# Sheet2.net
KiCad netlist of a schematic drawn in Altium Designer
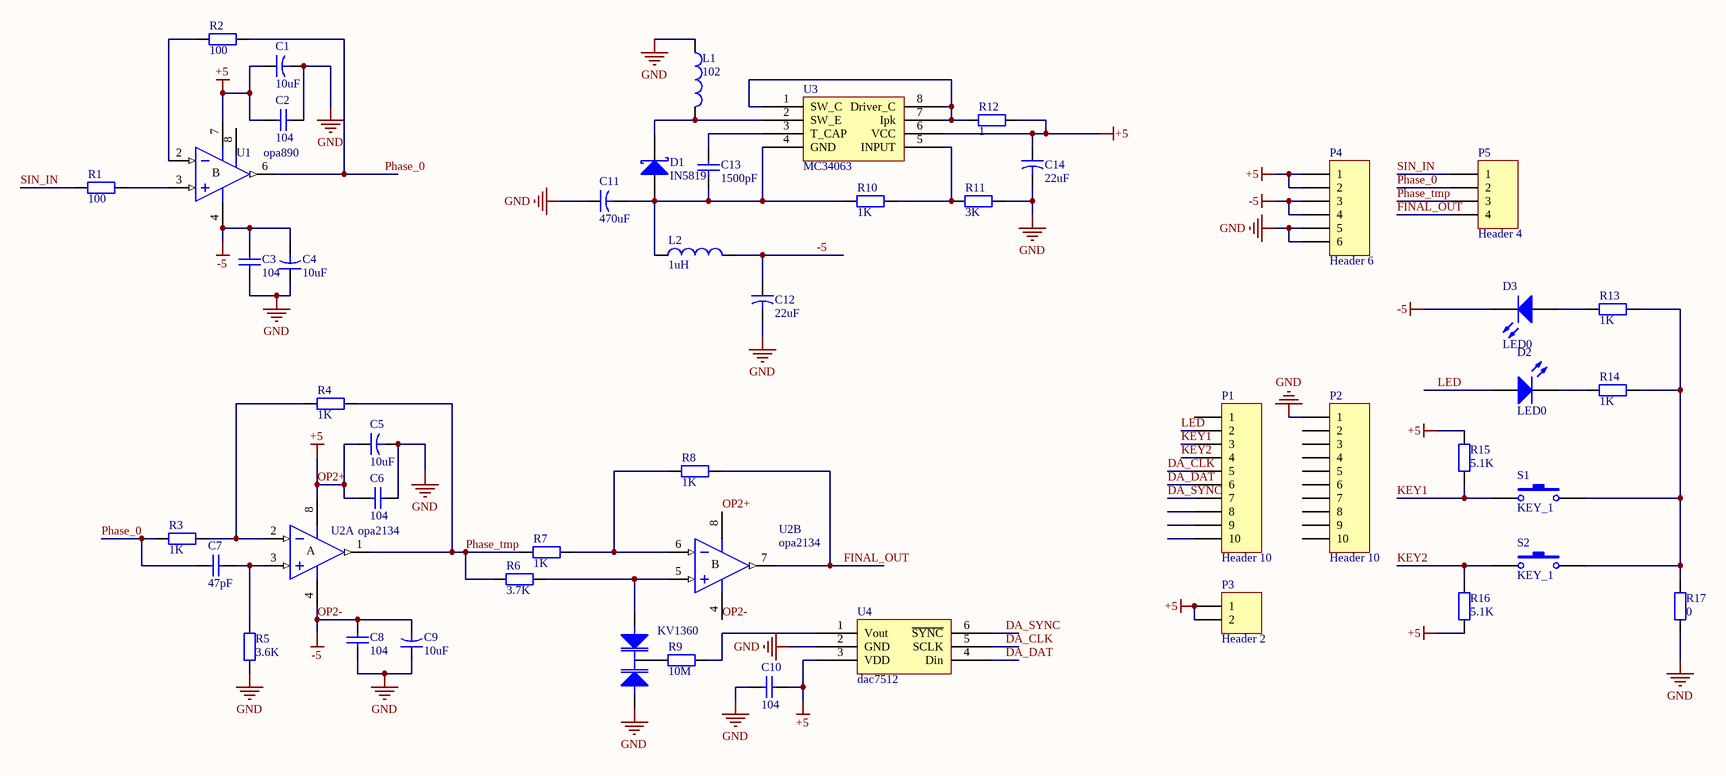
[diagram p0: Sheet2.SchDoc]

(export (version "E")
  (design (tool "Eeschema 10.0.6"))
  (components
    (comp (ref "*") (value "KV1360") (footprint "T092-3") (libsource (lib "暑期学校") (part "KV1360")))
    (comp (ref "C1")
      (value "10uF")
      (footprint "1812")
      (description "Capacitor")
      (fields (field (name "Comment") "Cap2") (field (name "PUBLISHER") "Altium Limited"))
      (libsource (lib "Miscellaneous Devices") (part "Cap2"))
    )
    (comp (ref "C2")
      (value "104")
      (footprint "C0805")
      (description "Capacitor")
      (fields (field (name "Comment") "Cap") (field (name "PUBLISHER") "Altium Limited"))
      (libsource (lib "Miscellaneous Devices") (part "Cap"))
    )
    (comp (ref "C3")
      (value "104")
      (footprint "C0805")
      (description "Capacitor")
      (fields (field (name "Comment") "Cap") (field (name "PUBLISHER") "Altium Limited"))
      (libsource (lib "Miscellaneous Devices") (part "Cap"))
    )
    (comp (ref "C4")
      (value "10uF")
      (footprint "1812")
      (description "Capacitor")
      (fields (field (name "Comment") "Cap2") (field (name "PUBLISHER") "Altium Limited"))
      (libsource (lib "Miscellaneous Devices") (part "Cap2"))
    )
    (comp (ref "C5")
      (value "10uF")
      (footprint "1812")
      (description "Capacitor")
      (fields (field (name "Comment") "Cap2") (field (name "PUBLISHER") "Altium Limited"))
      (libsource (lib "Miscellaneous Devices") (part "Cap2"))
    )
    (comp (ref "C6")
      (value "104")
      (footprint "C0805")
      (description "Capacitor")
      (fields (field (name "Comment") "Cap") (field (name "PUBLISHER") "Altium Limited"))
      (libsource (lib "Miscellaneous Devices") (part "Cap"))
    )
    (comp (ref "C7")
      (value "47pF")
      (footprint "C0805")
      (description "Capacitor")
      (fields (field (name "Comment") "Cap") (field (name "PUBLISHER") "Altium Limited"))
      (libsource (lib "Miscellaneous Devices") (part "Cap"))
    )
    (comp (ref "C8")
      (value "104")
      (footprint "C0805")
      (description "Capacitor")
      (fields (field (name "Comment") "Cap") (field (name "PUBLISHER") "Altium Limited"))
      (libsource (lib "Miscellaneous Devices") (part "Cap"))
    )
    (comp (ref "C9")
      (value "10uF")
      (footprint "1812")
      (description "Capacitor")
      (fields (field (name "Comment") "Cap2") (field (name "PUBLISHER") "Altium Limited"))
      (libsource (lib "Miscellaneous Devices") (part "Cap2"))
    )
    (comp (ref "C10")
      (value "104")
      (footprint "C0805")
      (description "Capacitor")
      (fields (field (name "Comment") "Cap") (field (name "PUBLISHER") "Altium Limited"))
      (libsource (lib "Miscellaneous Devices") (part "Cap"))
    )
    (comp (ref "C11")
      (value "470uF")
      (footprint "CAPPR2-5x6.8")
      (description "Capacitor")
      (fields (field (name "Comment") "Cap2") (field (name "PUBLISHER") "Altium Limited"))
      (libsource (lib "Miscellaneous Devices") (part "Cap2"))
    )
    (comp (ref "C12")
      (value "22uF")
      (footprint "CAPPR2-5x6.8")
      (description "Capacitor")
      (fields (field (name "Comment") "Cap2") (field (name "PUBLISHER") "Altium Limited"))
      (libsource (lib "Miscellaneous Devices") (part "Cap2"))
    )
    (comp (ref "C13")
      (value "1500pF")
      (footprint "C0805")
      (description "Capacitor")
      (fields (field (name "Comment") "Cap") (field (name "PUBLISHER") "Altium Limited"))
      (libsource (lib "Miscellaneous Devices") (part "Cap"))
    )
    (comp (ref "C14")
      (value "22uF")
      (footprint "CAPPR2-5x6.8")
      (description "Capacitor")
      (fields (field (name "Comment") "Cap2") (field (name "PUBLISHER") "Altium Limited"))
      (libsource (lib "Miscellaneous Devices") (part "Cap2"))
    )
    (comp (ref "D1")
      (value "IN5819")
      (footprint "1812")
      (description "Schottky Rectifier")
      (fields (field (name "PUBLISHER") "Altium Limited"))
      (libsource (lib "Miscellaneous Devices") (part "Diode 11DQ03"))
    )
    (comp (ref "D2")
      (value "LED0")
      (footprint "C0805")
      (description "Typical INFRARED GaAs LED")
      (fields (field (name "PUBLISHER") "Altium Limited"))
      (libsource (lib "Miscellaneous Devices") (part "LED0"))
    )
    (comp (ref "D3")
      (value "LED0")
      (footprint "C0805")
      (description "Typical INFRARED GaAs LED")
      (fields (field (name "PUBLISHER") "Altium Limited"))
      (libsource (lib "Miscellaneous Devices") (part "LED0"))
    )
    (comp (ref "L1")
      (value "102")
      (footprint "RB5-10.5")
      (description "Inductor")
      (fields (field (name "PUBLISHER") "Altium Limited"))
      (libsource (lib "Miscellaneous Devices") (part "Inductor"))
    )
    (comp (ref "L2")
      (value "1uH")
      (footprint "2012[0805]")
      (description "Inductor")
      (fields (field (name "PUBLISHER") "Altium Limited"))
      (libsource (lib "Miscellaneous Devices") (part "Inductor"))
    )
    (comp (ref "P1")
      (value "Header 10")
      (footprint "HDR1X10")
      (description "Header, 10-Pin")
      (fields (field (name "PUBLISHER") "Altium Limited"))
      (libsource (lib "Miscellaneous Connectors") (part "Header 10"))
    )
    (comp (ref "P2")
      (value "Header 10")
      (footprint "HDR1X10")
      (description "Header, 10-Pin")
      (fields (field (name "PUBLISHER") "Altium Limited"))
      (libsource (lib "Miscellaneous Connectors") (part "Header 10"))
    )
    (comp (ref "P3")
      (value "Header 2")
      (footprint "HDR1X2")
      (description "Header, 2-Pin")
      (fields (field (name "PUBLISHER") "Altium Limited"))
      (libsource (lib "Miscellaneous Connectors") (part "Header 2"))
    )
    (comp (ref "P4")
      (value "Header 6")
      (footprint "HDR1X6")
      (description "Header, 6-Pin")
      (fields (field (name "PUBLISHER") "Altium Limited"))
      (libsource (lib "Miscellaneous Connectors") (part "Header 6"))
    )
    (comp (ref "P5")
      (value "Header 4")
      (footprint "HDR1X4")
      (description "Header, 4-Pin")
      (fields (field (name "PUBLISHER") "Altium Limited"))
      (libsource (lib "Miscellaneous Connectors") (part "Header 4"))
    )
    (comp (ref "R1")
      (value "100")
      (footprint "2012[0805]")
      (description "Resistor")
      (fields (field (name "Comment") "Res2") (field (name "PUBLISHER") "Altium Limited"))
      (libsource (lib "") (part "Res2_1"))
    )
    (comp (ref "R2")
      (value "100")
      (footprint "2012[0805]")
      (description "Resistor")
      (fields (field (name "Comment") "Res2") (field (name "PUBLISHER") "Altium Limited"))
      (libsource (lib "") (part "Res2_1"))
    )
    (comp (ref "R3")
      (value "1K")
      (footprint "2012[0805]")
      (description "Resistor")
      (fields (field (name "Comment") "Res2") (field (name "PUBLISHER") "Altium Limited"))
      (libsource (lib "") (part "Res2_1"))
    )
    (comp (ref "R4")
      (value "1K")
      (footprint "2012[0805]")
      (description "Resistor")
      (fields (field (name "Comment") "Res2") (field (name "PUBLISHER") "Altium Limited"))
      (libsource (lib "") (part "Res2_1"))
    )
    (comp (ref "R5")
      (value "3.6K")
      (footprint "2012[0805]")
      (description "Resistor")
      (fields (field (name "Comment") "Res2") (field (name "PUBLISHER") "Altium Limited"))
      (libsource (lib "Miscellaneous Devices") (part "Res2"))
    )
    (comp (ref "R6")
      (value "3.7K")
      (footprint "2012[0805]")
      (description "Resistor")
      (fields (field (name "Comment") "Res2") (field (name "PUBLISHER") "Altium Limited"))
      (libsource (lib "") (part "Res2_1"))
    )
    (comp (ref "R7")
      (value "1K")
      (footprint "2012[0805]")
      (description "Resistor")
      (fields (field (name "Comment") "Res2") (field (name "PUBLISHER") "Altium Limited"))
      (libsource (lib "") (part "Res2_1"))
    )
    (comp (ref "R8")
      (value "1K")
      (footprint "2012[0805]")
      (description "Resistor")
      (fields (field (name "Comment") "Res2") (field (name "PUBLISHER") "Altium Limited"))
      (libsource (lib "") (part "Res2_1"))
    )
    (comp (ref "R9")
      (value "10M")
      (footprint "2012[0805]")
      (description "Resistor")
      (fields (field (name "Comment") "Res2") (field (name "PUBLISHER") "Altium Limited"))
      (libsource (lib "") (part "Res2_2"))
    )
    (comp (ref "R10")
      (value "1K")
      (footprint "2012[0805]")
      (description "Resistor")
      (fields (field (name "Comment") "Res2") (field (name "PUBLISHER") "Altium Limited"))
      (libsource (lib "") (part "Res2_1"))
    )
    (comp (ref "R11")
      (value "3K")
      (footprint "2012[0805]")
      (description "Resistor")
      (fields (field (name "Comment") "Res2") (field (name "PUBLISHER") "Altium Limited"))
      (libsource (lib "") (part "Res2_2"))
    )
    (comp (ref "R12")
      (value "1")
      (footprint "2012[0805]")
      (description "Resistor")
      (fields (field (name "Comment") "Res2") (field (name "PUBLISHER") "Altium Limited"))
      (libsource (lib "") (part "Res2_1"))
    )
    (comp (ref "R13")
      (value "1K")
      (footprint "2012[0805]")
      (description "Resistor")
      (fields (field (name "Comment") "Res2") (field (name "PUBLISHER") "Altium Limited"))
      (libsource (lib "") (part "Res2_2"))
    )
    (comp (ref "R14")
      (value "1K")
      (footprint "2012[0805]")
      (description "Resistor")
      (fields (field (name "Comment") "Res2") (field (name "PUBLISHER") "Altium Limited"))
      (libsource (lib "") (part "Res2_2"))
    )
    (comp (ref "R15")
      (value "5.1K")
      (footprint "2012[0805]")
      (description "Resistor")
      (fields (field (name "Comment") "Res2") (field (name "PUBLISHER") "Altium Limited"))
      (libsource (lib "") (part "Res2_3"))
    )
    (comp (ref "R16")
      (value "5.1K")
      (footprint "2012[0805]")
      (description "Resistor")
      (fields (field (name "Comment") "Res2") (field (name "PUBLISHER") "Altium Limited"))
      (libsource (lib "") (part "Res2_3"))
    )
    (comp (ref "R17")
      (value "0")
      (footprint "2012[0805]")
      (description "Resistor")
      (fields (field (name "Comment") "Res2") (field (name "PUBLISHER") "Altium Limited"))
      (libsource (lib "Miscellaneous Devices") (part "Res2"))
    )
    (comp (ref "S1")
      (value "KEY_1")
      (footprint "SW")
      (description "Switch")
      (fields (field (name "PUBLISHER") "Altium Limited"))
      (libsource (lib "Miscellaneous Devices") (part "SW-PB"))
    )
    (comp (ref "S2")
      (value "KEY_1")
      (footprint "SW")
      (description "Switch")
      (fields (field (name "PUBLISHER") "Altium Limited"))
      (libsource (lib "Miscellaneous Devices") (part "SW-PB"))
    )
    (comp (ref "U1") (value "opa890") (footprint "SO-8_N") (libsource (lib "暑期学校") (part "opa890")))
    (comp (ref "U2") (value "opa2134") (footprint "SO-8_N") (libsource (lib "暑期学校") (part "opa2134")))
    (comp (ref "U3") (value "MC34063") (footprint "SO-8_N") (libsource (lib "暑期学校") (part "MC34063")))
    (comp (ref "U4") (value "dac7512") (footprint "SOT23-6") (libsource (lib "暑期学校") (part "dac7512")))
  )
  (nets
    (net (code "1") (name "+5") (class "Default")
      (node (ref "C1") (pin "1") (pinfunction "1_1") (pintype "passive"))
      (node (ref "C10") (pin "2") (pinfunction "2_2") (pintype "passive"))
      (node (ref "C14") (pin "1") (pinfunction "1_1") (pintype "passive"))
      (node (ref "C2") (pin "1") (pinfunction "1_1") (pintype "passive"))
      (node (ref "C5") (pin "1") (pinfunction "1_1") (pintype "passive"))
      (node (ref "C6") (pin "1") (pinfunction "1_1") (pintype "passive"))
      (node (ref "P3") (pin "1") (pinfunction "1_1") (pintype "passive"))
      (node (ref "P3") (pin "2") (pinfunction "2_2") (pintype "passive"))
      (node (ref "P4") (pin "1") (pinfunction "1_1") (pintype "passive"))
      (node (ref "P4") (pin "2") (pinfunction "2_2") (pintype "passive"))
      (node (ref "R12") (pin "2") (pinfunction "2_2") (pintype "passive"))
      (node (ref "R15") (pin "1") (pinfunction "1_1") (pintype "passive"))
      (node (ref "R16") (pin "2") (pinfunction "2_2") (pintype "passive"))
      (node (ref "U1") (pin "7") (pinfunction "V+_7") (pintype "power_in"))
      (node (ref "U2") (pin "8") (pinfunction "V+_8") (pintype "power_in"))
      (node (ref "U3") (pin "6") (pinfunction "VCC_6") (pintype "passive"))
      (node (ref "U4") (pin "3") (pinfunction "VDD_3") (pintype "passive"))
    )
    (net (code "2") (name "-5") (class "Default")
      (node (ref "C12") (pin "1") (pinfunction "1_1") (pintype "passive"))
      (node (ref "C3") (pin "2") (pinfunction "2_2") (pintype "passive"))
      (node (ref "C4") (pin "2") (pinfunction "2_2") (pintype "passive"))
      (node (ref "C8") (pin "2") (pinfunction "2_2") (pintype "passive"))
      (node (ref "C9") (pin "2") (pinfunction "2_2") (pintype "passive"))
      (node (ref "D3") (pin "2") (pinfunction "K_2") (pintype "passive"))
      (node (ref "L2") (pin "2") (pinfunction "2_2") (pintype "passive"))
      (node (ref "P4") (pin "3") (pinfunction "3_3") (pintype "passive"))
      (node (ref "P4") (pin "4") (pinfunction "4_4") (pintype "passive"))
      (node (ref "U1") (pin "4") (pinfunction "V-_4") (pintype "power_in"))
      (node (ref "U2") (pin "4") (pinfunction "V-_4") (pintype "power_in"))
    )
    (net (code "3") (name "/DA_CLK") (class "Default")
      (node (ref "P1") (pin "5") (pinfunction "5_5") (pintype "passive"))
      (node (ref "U4") (pin "5") (pinfunction "SCLK_5") (pintype "passive"))
    )
    (net (code "4") (name "/DA_DAT") (class "Default")
      (node (ref "P1") (pin "6") (pinfunction "6_6") (pintype "passive"))
      (node (ref "U4") (pin "4") (pinfunction "Din_4") (pintype "passive"))
    )
    (net (code "5") (name "/DA_SYNC") (class "Default")
      (node (ref "P1") (pin "7") (pinfunction "7_7") (pintype "passive"))
      (node (ref "U4") (pin "6") (pinfunction "~{SYNC}_6") (pintype "passive"))
    )
    (net (code "6") (name "/FINAL_OUT") (class "Default")
      (node (ref "P5") (pin "4") (pinfunction "4_4") (pintype "passive"))
      (node (ref "R8") (pin "2") (pinfunction "2_2") (pintype "passive"))
      (node (ref "U2") (pin "7") (pinfunction "OUT_7") (pintype "output"))
    )
    (net (code "7") (name "/KEY1") (class "Default")
      (node (ref "P1") (pin "3") (pinfunction "3_3") (pintype "passive"))
      (node (ref "R15") (pin "2") (pinfunction "2_2") (pintype "passive"))
      (node (ref "S1") (pin "1") (pinfunction "1_1") (pintype "passive"))
    )
    (net (code "8") (name "/KEY2") (class "Default")
      (node (ref "P1") (pin "4") (pinfunction "4_4") (pintype "passive"))
      (node (ref "R16") (pin "1") (pinfunction "1_1") (pintype "passive"))
      (node (ref "S2") (pin "1") (pinfunction "1_1") (pintype "passive"))
    )
    (net (code "9") (name "/LED") (class "Default")
      (node (ref "D2") (pin "1") (pinfunction "A_1") (pintype "passive"))
      (node (ref "P1") (pin "2") (pinfunction "2_2") (pintype "passive"))
    )
    (net (code "10") (name "/Phase_0") (class "Default")
      (node (ref "C7") (pin "2") (pinfunction "2_2") (pintype "passive"))
      (node (ref "P5") (pin "2") (pinfunction "2_2") (pintype "passive"))
      (node (ref "R2") (pin "2") (pinfunction "2_2") (pintype "passive"))
      (node (ref "R3") (pin "1") (pinfunction "1_1") (pintype "passive"))
      (node (ref "U1") (pin "6") (pinfunction "OUT_6") (pintype "output"))
    )
    (net (code "11") (name "/Phase_tmp") (class "Default")
      (node (ref "P5") (pin "3") (pinfunction "3_3") (pintype "passive"))
      (node (ref "R4") (pin "2") (pinfunction "2_2") (pintype "passive"))
      (node (ref "R6") (pin "1") (pinfunction "1_1") (pintype "passive"))
      (node (ref "R7") (pin "1") (pinfunction "1_1") (pintype "passive"))
      (node (ref "U2") (pin "1") (pinfunction "OUT_1") (pintype "output"))
    )
    (net (code "12") (name "/SIN_IN") (class "Default")
      (node (ref "P5") (pin "1") (pinfunction "1_1") (pintype "passive"))
      (node (ref "R1") (pin "1") (pinfunction "1_1") (pintype "passive"))
    )
    (net (code "13") (name "GND") (class "Default")
      (node (ref "*") (pin "1") (pinfunction "1_1") (pintype "passive"))
      (node (ref "C1") (pin "2") (pinfunction "2_2") (pintype "passive"))
      (node (ref "C10") (pin "1") (pinfunction "1_1") (pintype "passive"))
      (node (ref "C11") (pin "1") (pinfunction "1_1") (pintype "passive"))
      (node (ref "C12") (pin "2") (pinfunction "2_2") (pintype "passive"))
      (node (ref "C14") (pin "2") (pinfunction "2_2") (pintype "passive"))
      (node (ref "C2") (pin "2") (pinfunction "2_2") (pintype "passive"))
      (node (ref "C3") (pin "1") (pinfunction "1_1") (pintype "passive"))
      (node (ref "C4") (pin "1") (pinfunction "1_1") (pintype "passive"))
      (node (ref "C5") (pin "2") (pinfunction "2_2") (pintype "passive"))
      (node (ref "C6") (pin "2") (pinfunction "2_2") (pintype "passive"))
      (node (ref "C8") (pin "1") (pinfunction "1_1") (pintype "passive"))
      (node (ref "C9") (pin "1") (pinfunction "1_1") (pintype "passive"))
      (node (ref "L1") (pin "1") (pinfunction "1_1") (pintype "passive"))
      (node (ref "P2") (pin "1") (pinfunction "1_1") (pintype "passive"))
      (node (ref "P4") (pin "5") (pinfunction "5_5") (pintype "passive"))
      (node (ref "P4") (pin "6") (pinfunction "6_6") (pintype "passive"))
      (node (ref "R11") (pin "1") (pinfunction "1_1") (pintype "passive"))
      (node (ref "R17") (pin "1") (pinfunction "1_1") (pintype "passive"))
      (node (ref "R5") (pin "1") (pinfunction "1_1") (pintype "passive"))
      (node (ref "U4") (pin "2") (pinfunction "GND_2") (pintype "passive"))
    )
    (net (code "14") (name "Net-(*-Pad2)") (class "Default")
      (node (ref "*") (pin "2") (pinfunction "2_2") (pintype "passive"))
      (node (ref "R9") (pin "2") (pinfunction "2_2") (pintype "passive"))
    )
    (net (code "15") (name "Net-(D1-A)") (class "Default")
      (node (ref "C11") (pin "2") (pinfunction "2_2") (pintype "passive"))
      (node (ref "C13") (pin "1") (pinfunction "1_1") (pintype "passive"))
      (node (ref "D1") (pin "1") (pinfunction "A_1") (pintype "passive"))
      (node (ref "L2") (pin "1") (pinfunction "1_1") (pintype "passive"))
      (node (ref "R10") (pin "1") (pinfunction "1_1") (pintype "passive"))
      (node (ref "U3") (pin "4") (pinfunction "GND_4") (pintype "passive"))
    )
    (net (code "16") (name "Net-(D1-K)") (class "Default")
      (node (ref "D1") (pin "2") (pinfunction "K_2") (pintype "passive"))
      (node (ref "L1") (pin "2") (pinfunction "2_2") (pintype "passive"))
      (node (ref "U3") (pin "2") (pinfunction "SW_E_2") (pintype "passive"))
    )
    (net (code "17") (name "Net-(D2-K)") (class "Default")
      (node (ref "D2") (pin "2") (pinfunction "K_2") (pintype "passive"))
      (node (ref "R14") (pin "2") (pinfunction "2_2") (pintype "passive"))
    )
    (net (code "18") (name "Net-(D3-A)") (class "Default")
      (node (ref "D3") (pin "1") (pinfunction "A_1") (pintype "passive"))
      (node (ref "R13") (pin "2") (pinfunction "2_2") (pintype "passive"))
    )
    (net (code "19") (name "Net-(R13-Pad1)") (class "Default")
      (node (ref "R13") (pin "1") (pinfunction "1_1") (pintype "passive"))
      (node (ref "R14") (pin "1") (pinfunction "1_1") (pintype "passive"))
      (node (ref "R17") (pin "2") (pinfunction "2_2") (pintype "passive"))
      (node (ref "S1") (pin "2") (pinfunction "2_2") (pintype "passive"))
      (node (ref "S2") (pin "2") (pinfunction "2_2") (pintype "passive"))
    )
    (net (code "20") (name "Net-(U1-IN+)") (class "Default")
      (node (ref "R1") (pin "2") (pinfunction "2_2") (pintype "passive"))
      (node (ref "U1") (pin "3") (pinfunction "IN+_3") (pintype "input"))
    )
    (net (code "21") (name "Net-(U1-IN-)") (class "Default")
      (node (ref "R2") (pin "1") (pinfunction "1_1") (pintype "passive"))
      (node (ref "U1") (pin "2") (pinfunction "IN-_2") (pintype "input"))
    )
    (net (code "22") (name "Net-(U2A-IN+)") (class "Default")
      (node (ref "C7") (pin "1") (pinfunction "1_1") (pintype "passive"))
      (node (ref "R5") (pin "2") (pinfunction "2_2") (pintype "passive"))
      (node (ref "U2") (pin "3") (pinfunction "IN+_3") (pintype "input"))
    )
    (net (code "23") (name "Net-(U2A-IN-)") (class "Default")
      (node (ref "R3") (pin "2") (pinfunction "2_2") (pintype "passive"))
      (node (ref "R4") (pin "1") (pinfunction "1_1") (pintype "passive"))
      (node (ref "U2") (pin "2") (pinfunction "IN-_2") (pintype "input"))
    )
    (net (code "24") (name "Net-(U2B-IN+)") (class "Default")
      (node (ref "*") (pin "3") (pinfunction "3_3") (pintype "passive"))
      (node (ref "R6") (pin "2") (pinfunction "2_2") (pintype "passive"))
      (node (ref "U2") (pin "5") (pinfunction "IN+_5") (pintype "input"))
    )
    (net (code "25") (name "Net-(U2B-IN-)") (class "Default")
      (node (ref "R7") (pin "2") (pinfunction "2_2") (pintype "passive"))
      (node (ref "R8") (pin "1") (pinfunction "1_1") (pintype "passive"))
      (node (ref "U2") (pin "6") (pinfunction "IN-_6") (pintype "input"))
    )
    (net (code "26") (name "Net-(U3-Driver_C)") (class "Default")
      (node (ref "R12") (pin "1") (pinfunction "1_1") (pintype "passive"))
      (node (ref "U3") (pin "1") (pinfunction "SW_C_1") (pintype "passive"))
      (node (ref "U3") (pin "7") (pinfunction "Ipk_7") (pintype "passive"))
      (node (ref "U3") (pin "8") (pinfunction "Driver_C_8") (pintype "passive"))
    )
    (net (code "27") (name "Net-(U3-INPUT)") (class "Default")
      (node (ref "R10") (pin "2") (pinfunction "2_2") (pintype "passive"))
      (node (ref "R11") (pin "2") (pinfunction "2_2") (pintype "passive"))
      (node (ref "U3") (pin "5") (pinfunction "INPUT_5") (pintype "passive"))
    )
    (net (code "28") (name "Net-(U3-T_CAP)") (class "Default")
      (node (ref "C13") (pin "2") (pinfunction "2_2") (pintype "passive"))
      (node (ref "U3") (pin "3") (pinfunction "T_CAP_3") (pintype "passive"))
    )
    (net (code "29") (name "Net-(U4-Vout)") (class "Default")
      (node (ref "R9") (pin "1") (pinfunction "1_1") (pintype "passive"))
      (node (ref "U4") (pin "1") (pinfunction "Vout_1") (pintype "passive"))
    )
    (net (code "30") (name "unconnected-(P1-Pad1)") (class "Default")
      (node (ref "P1") (pin "1") (pinfunction "1_1") (pintype "passive"))
    )
    (net (code "31") (name "unconnected-(P1-Pad8)") (class "Default")
      (node (ref "P1") (pin "8") (pinfunction "8_8") (pintype "passive"))
    )
    (net (code "32") (name "unconnected-(P1-Pad9)") (class "Default")
      (node (ref "P1") (pin "9") (pinfunction "9_9") (pintype "passive"))
    )
    (net (code "33") (name "unconnected-(P1-Pad10)") (class "Default")
      (node (ref "P1") (pin "10") (pinfunction "10_10") (pintype "passive"))
    )
    (net (code "34") (name "unconnected-(P2-Pad2)") (class "Default")
      (node (ref "P2") (pin "2") (pinfunction "2_2") (pintype "passive"))
    )
    (net (code "35") (name "unconnected-(P2-Pad3)") (class "Default")
      (node (ref "P2") (pin "3") (pinfunction "3_3") (pintype "passive"))
    )
    (net (code "36") (name "unconnected-(P2-Pad4)") (class "Default")
      (node (ref "P2") (pin "4") (pinfunction "4_4") (pintype "passive"))
    )
    (net (code "37") (name "unconnected-(P2-Pad5)") (class "Default")
      (node (ref "P2") (pin "5") (pinfunction "5_5") (pintype "passive"))
    )
    (net (code "38") (name "unconnected-(P2-Pad6)") (class "Default")
      (node (ref "P2") (pin "6") (pinfunction "6_6") (pintype "passive"))
    )
    (net (code "39") (name "unconnected-(P2-Pad7)") (class "Default")
      (node (ref "P2") (pin "7") (pinfunction "7_7") (pintype "passive"))
    )
    (net (code "40") (name "unconnected-(P2-Pad8)") (class "Default")
      (node (ref "P2") (pin "8") (pinfunction "8_8") (pintype "passive"))
    )
    (net (code "41") (name "unconnected-(P2-Pad9)") (class "Default")
      (node (ref "P2") (pin "9") (pinfunction "9_9") (pintype "passive"))
    )
    (net (code "42") (name "unconnected-(P2-Pad10)") (class "Default")
      (node (ref "P2") (pin "10") (pinfunction "10_10") (pintype "passive"))
    )
    (net (code "43") (name "unconnected-(U1-~{DIS}-Pad8)") (class "Default")
      (node (ref "U1") (pin "8") (pinfunction "~{DIS}_8") (pintype "passive"))
    )
  )
)
